# SD_Card.net
KiCad netlist of a schematic drawn in Altium Designer
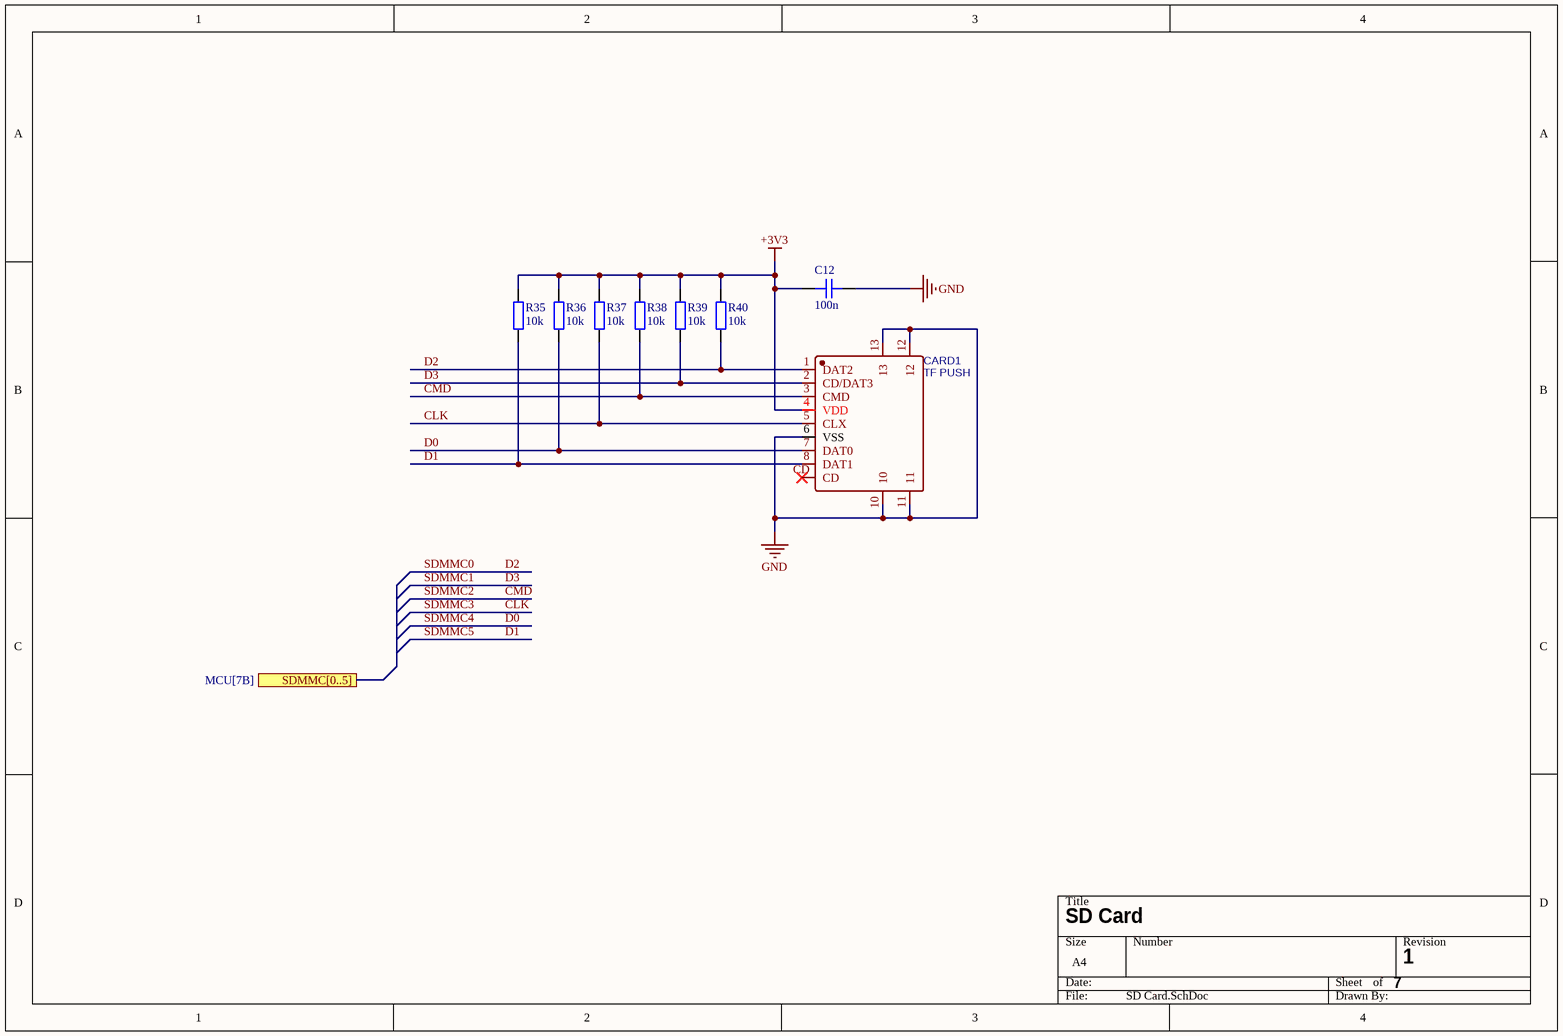
[diagram p0: SD Card.SchDoc]

(export (version "E")
  (design (tool "Eeschema 10.0.6"))
  (components
    (comp (ref "C12")
      (value "CL05B104KB54PNC")
      (footprint "CAP_0402")
      (description "Capacitor SMD 0402")
      (fields (field (name "RATING") "100n"))
      (libsource (lib "Schematic-Lib-PhilsLab") (part "CAP_0402"))
    )
    (comp (ref "CARD1")
      (value "TF PUSH")
      (footprint "TF-SMD_TF-PUSH")
      (fields (field (name "MANUFACTURER") "SHOU HAN(首韩)") (field (name "CONTRIBUTOR") "LCSC"))
      (libsource (lib "JLCPCB_parts_library") (part "TF PUSH"))
    )
    (comp (ref "R35")
      (value "10k")
      (footprint "RES_0402")
      (description "Resistor SMD 0402")
      (fields (field (name "Comment") "0402WGF1002TCE"))
      (libsource (lib "Schematic-Lib-PhilsLab") (part "RES_0402"))
    )
    (comp (ref "R36")
      (value "10k")
      (footprint "RES_0402")
      (description "Resistor SMD 0402")
      (fields (field (name "Comment") "0402WGF1002TCE"))
      (libsource (lib "Schematic-Lib-PhilsLab") (part "RES_0402"))
    )
    (comp (ref "R37")
      (value "10k")
      (footprint "RES_0402")
      (description "Resistor SMD 0402")
      (fields (field (name "Comment") "0402WGF1002TCE"))
      (libsource (lib "Schematic-Lib-PhilsLab") (part "RES_0402"))
    )
    (comp (ref "R38")
      (value "10k")
      (footprint "RES_0402")
      (description "Resistor SMD 0402")
      (fields (field (name "Comment") "0402WGF1002TCE"))
      (libsource (lib "Schematic-Lib-PhilsLab") (part "RES_0402"))
    )
    (comp (ref "R39")
      (value "10k")
      (footprint "RES_0402")
      (description "Resistor SMD 0402")
      (fields (field (name "Comment") "0402WGF1002TCE"))
      (libsource (lib "Schematic-Lib-PhilsLab") (part "RES_0402"))
    )
    (comp (ref "R40")
      (value "10k")
      (footprint "RES_0402")
      (description "Resistor SMD 0402")
      (fields (field (name "Comment") "0402WGF1002TCE"))
      (libsource (lib "Schematic-Lib-PhilsLab") (part "RES_0402"))
    )
  )
  (nets
    (net (code "1") (name "+3V3") (class "Default")
      (node (ref "C12") (pin "2") (pinfunction "2_2") (pintype "passive"))
      (node (ref "CARD1") (pin "4") (pinfunction "VDD_4") (pintype "passive"))
      (node (ref "R35") (pin "2") (pinfunction "2_2") (pintype "passive"))
      (node (ref "R36") (pin "2") (pinfunction "2_2") (pintype "passive"))
      (node (ref "R37") (pin "2") (pinfunction "2_2") (pintype "passive"))
      (node (ref "R38") (pin "2") (pinfunction "2_2") (pintype "passive"))
      (node (ref "R39") (pin "2") (pinfunction "2_2") (pintype "passive"))
      (node (ref "R40") (pin "2") (pinfunction "2_2") (pintype "passive"))
    )
    (net (code "2") (name "/SDMMC0") (class "Default")
      (node (ref "CARD1") (pin "1") (pinfunction "DAT2_1") (pintype "passive"))
      (node (ref "R40") (pin "1") (pinfunction "1_1") (pintype "passive"))
    )
    (net (code "3") (name "/SDMMC1") (class "Default")
      (node (ref "CARD1") (pin "2") (pinfunction "CD/DAT3_2") (pintype "passive"))
      (node (ref "R39") (pin "1") (pinfunction "1_1") (pintype "passive"))
    )
    (net (code "4") (name "/SDMMC2") (class "Default")
      (node (ref "CARD1") (pin "3") (pinfunction "CMD_3") (pintype "passive"))
      (node (ref "R38") (pin "1") (pinfunction "1_1") (pintype "passive"))
    )
    (net (code "5") (name "/SDMMC3") (class "Default")
      (node (ref "CARD1") (pin "5") (pinfunction "CLX_5") (pintype "passive"))
      (node (ref "R37") (pin "1") (pinfunction "1_1") (pintype "passive"))
    )
    (net (code "6") (name "/SDMMC4") (class "Default")
      (node (ref "CARD1") (pin "7") (pinfunction "DAT0_7") (pintype "passive"))
      (node (ref "R36") (pin "1") (pinfunction "1_1") (pintype "passive"))
    )
    (net (code "7") (name "/SDMMC5") (class "Default")
      (node (ref "CARD1") (pin "8") (pinfunction "DAT1_8") (pintype "passive"))
      (node (ref "R35") (pin "1") (pinfunction "1_1") (pintype "passive"))
    )
    (net (code "9") (name "GND") (class "Default")
      (node (ref "C12") (pin "1") (pinfunction "1_1") (pintype "passive"))
      (node (ref "CARD1") (pin "10") (pinfunction "10_10") (pintype "passive"))
      (node (ref "CARD1") (pin "11") (pinfunction "11_11") (pintype "passive"))
      (node (ref "CARD1") (pin "12") (pinfunction "12_12") (pintype "passive"))
      (node (ref "CARD1") (pin "13") (pinfunction "13_13") (pintype "passive"))
      (node (ref "CARD1") (pin "6") (pinfunction "VSS_6") (pintype "passive"))
    )
    (net (code "10") (name "unconnected-(CARD1-PadCD)") (class "Default")
      (node (ref "CARD1") (pin "CD") (pinfunction "CD_CD") (pintype "passive+no_connect"))
    )
  )
)
